# pad_ecg_schematic.net
KiCad netlist of a schematic drawn in Altium Designer
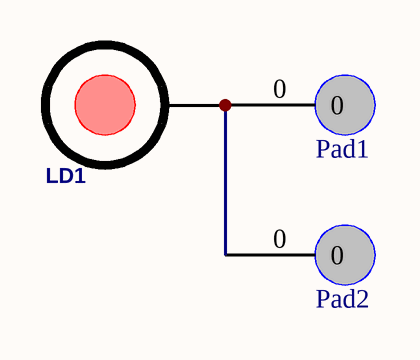
[diagram p0: pad_ecg_schematic.SchDoc]

(export (version "E")
  (design (tool "Eeschema 10.0.6"))
  (components
    (comp (ref "LD1")
      (value "ECG LEAD")
      (footprint "ECG PAD")
      (libsource (lib "VitalSignal EcgPpg Board") (part "ECG LEAD"))
    )
    (comp (ref "Pad1")
      (value "pad_ecg")
      (footprint "PcbLib1:pad_ecg")
      (libsource (lib "Schlib1") (part "pad_ecg"))
    )
    (comp (ref "Pad2")
      (value "pad_ecg")
      (footprint "PcbLib1:pad_ecg")
      (libsource (lib "Schlib1") (part "pad_ecg"))
    )
  )
  (nets
    (net (code "1") (name "Net-(LD1-Pad1)") (class "Default")
      (node (ref "LD1") (pin "1") (pinfunction "1_1") (pintype "passive"))
      (node (ref "Pad1") (pin "0") (pinfunction "0_0") (pintype "passive"))
      (node (ref "Pad2") (pin "0") (pinfunction "0_0") (pintype "passive"))
    )
  )
)
